# ADC.net
KiCad netlist of a schematic drawn in EasyEDA Pro
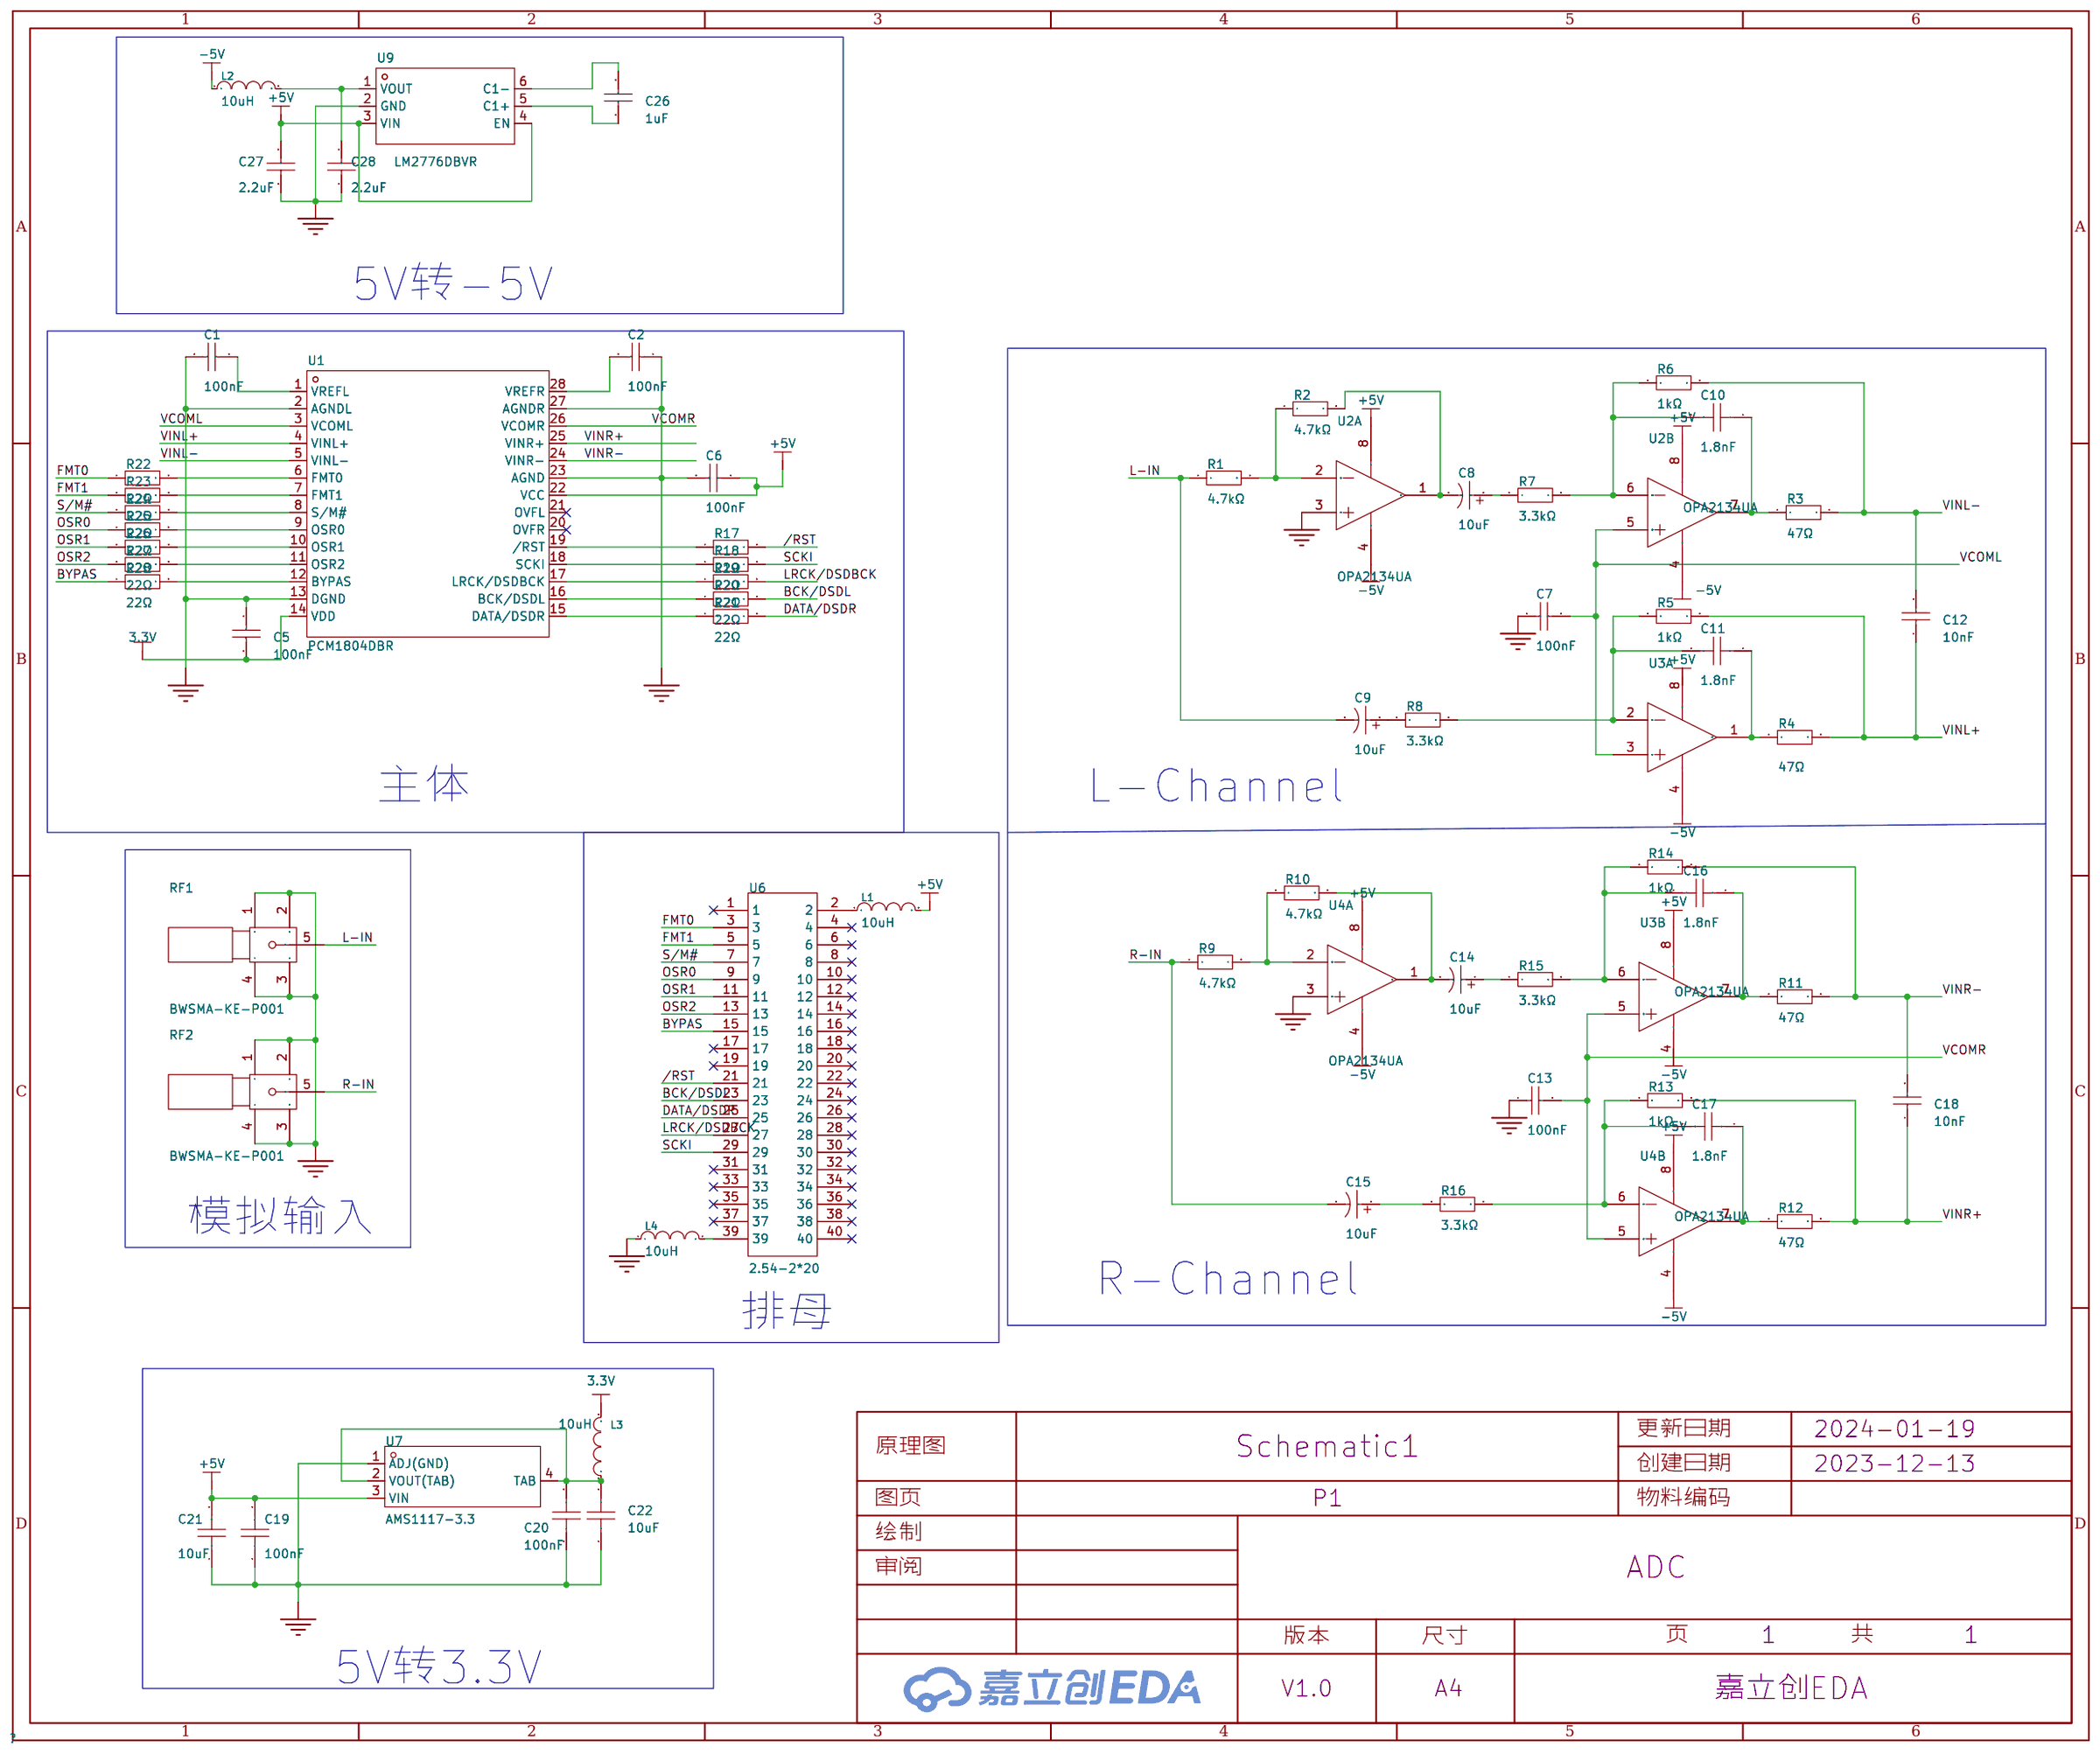
[diagram p0: schematic sheet]

(export (version "E")
  (design (tool "Eeschema 10.0.6"))
  (components
    (comp (ref "C1")
      (value "100nF")
      (footprint "easyedapro:C0805")
      (description "容值:100nF;精度:±10%;额定电压:50V;材质(温度系数):X7R;")
      (fields
        (field (name "Manufacturer Part") "CC0805KRX7R9BB104")
        (field (name "Manufacturer") "YAGEO(国巨)")
      )
      (libsource (lib "easyedapro") (part "CC0805KRX7R9BB104"))
    )
    (comp (ref "C2")
      (value "100nF")
      (footprint "easyedapro:C0805")
      (description "容值:100nF;精度:±10%;额定电压:50V;材质(温度系数):X7R;")
      (fields
        (field (name "Manufacturer Part") "CC0805KRX7R9BB104")
        (field (name "Manufacturer") "YAGEO(国巨)")
      )
      (libsource (lib "easyedapro") (part "CC0805KRX7R9BB104"))
    )
    (comp (ref "C5")
      (value "100nF")
      (footprint "easyedapro:C0805")
      (description "容值:100nF;精度:±10%;额定电压:50V;材质(温度系数):X7R;")
      (fields
        (field (name "Manufacturer Part") "CC0805KRX7R9BB104")
        (field (name "Manufacturer") "YAGEO(国巨)")
      )
      (libsource (lib "easyedapro") (part "CC0805KRX7R9BB104"))
    )
    (comp (ref "C6")
      (value "100nF")
      (footprint "easyedapro:C0805")
      (description "容值:100nF;精度:±10%;额定电压:50V;材质(温度系数):X7R;")
      (fields
        (field (name "Manufacturer Part") "CC0805KRX7R9BB104")
        (field (name "Manufacturer") "YAGEO(国巨)")
      )
      (libsource (lib "easyedapro") (part "CC0805KRX7R9BB104"))
    )
    (comp (ref "C7")
      (value "100nF")
      (footprint "easyedapro:C0805")
      (description "容值:100nF;精度:±10%;额定电压:50V;材质(温度系数):X7R;")
      (fields
        (field (name "Manufacturer Part") "CC0805KRX7R9BB104")
        (field (name "Manufacturer") "YAGEO(国巨)")
      )
      (libsource (lib "easyedapro") (part "CC0805KRX7R9BB104"))
    )
    (comp (ref "C8")
      (value "10uF")
      (footprint "easyedapro:CAP-SMD_BD6.3-L6.6-W6.6-FD")
      (description "容值:10uF;精度:±20%;额定电压:100V;纹波电流:38mA@120Hz;等效串联电阻:-;")
      (fields (field (name "Manufacturer Part") "RVT2A100M0607") (field (name "Manufacturer") "ROQANG(容强)"))
      (libsource (lib "easyedapro") (part "RVT2A100M0607"))
    )
    (comp (ref "C9")
      (value "10uF")
      (footprint "easyedapro:CAP-SMD_BD6.3-L6.6-W6.6-FD")
      (description "容值:10uF;精度:±20%;额定电压:100V;纹波电流:38mA@120Hz;等效串联电阻:-;")
      (fields (field (name "Manufacturer Part") "RVT2A100M0607") (field (name "Manufacturer") "ROQANG(容强)"))
      (libsource (lib "easyedapro") (part "RVT2A100M0607"))
    )
    (comp (ref "C10")
      (value "1.8nF")
      (footprint "easyedapro:C0201")
      (description "容值:1.8nF;精度:±10%;额定电压:25V;材质(温度系数):X7R;")
      (fields
        (field (name "Manufacturer Part") "CC0805JRNPO9BN182")
        (field (name "Manufacturer") "YAGEO(国巨)")
      )
      (libsource (lib "easyedapro") (part "GRM033R71E182KA12D"))
    )
    (comp (ref "C11")
      (value "1.8nF")
      (footprint "easyedapro:C0201")
      (description "容值:1.8nF;精度:±10%;额定电压:25V;材质(温度系数):X7R;")
      (fields
        (field (name "Manufacturer Part") "CC0805JRNPO9BN182")
        (field (name "Manufacturer") "YAGEO(国巨)")
      )
      (libsource (lib "easyedapro") (part "GRM033R71E182KA12D"))
    )
    (comp (ref "C12")
      (value "10nF")
      (footprint "easyedapro:C0402")
      (description "容值:10nF;精度:±10%;额定电压:50V;材质(温度系数):X7R;")
      (fields
        (field (name "Manufacturer Part") "CL21B103KBANNNC")
        (field (name "Manufacturer") "SAMSUNG(三星)")
      )
      (libsource (lib "easyedapro") (part "CC0402KRX7R9BB103"))
    )
    (comp (ref "C13")
      (value "100nF")
      (footprint "easyedapro:C0805")
      (description "容值:100nF;精度:±10%;额定电压:50V;材质(温度系数):X7R;")
      (fields
        (field (name "Manufacturer Part") "CC0805KRX7R9BB104")
        (field (name "Manufacturer") "YAGEO(国巨)")
      )
      (libsource (lib "easyedapro") (part "CC0805KRX7R9BB104"))
    )
    (comp (ref "C14")
      (value "10uF")
      (footprint "easyedapro:CAP-SMD_BD6.3-L6.6-W6.6-FD")
      (description "容值:10uF;精度:±20%;额定电压:100V;纹波电流:38mA@120Hz;等效串联电阻:-;")
      (fields (field (name "Manufacturer Part") "RVT2A100M0607") (field (name "Manufacturer") "ROQANG(容强)"))
      (libsource (lib "easyedapro") (part "RVT2A100M0607"))
    )
    (comp (ref "C15")
      (value "10uF")
      (footprint "easyedapro:CAP-SMD_BD6.3-L6.6-W6.6-FD")
      (description "容值:10uF;精度:±20%;额定电压:100V;纹波电流:38mA@120Hz;等效串联电阻:-;")
      (fields (field (name "Manufacturer Part") "RVT2A100M0607") (field (name "Manufacturer") "ROQANG(容强)"))
      (libsource (lib "easyedapro") (part "RVT2A100M0607"))
    )
    (comp (ref "C16")
      (value "1.8nF")
      (footprint "easyedapro:C0201")
      (description "容值:1.8nF;精度:±10%;额定电压:25V;材质(温度系数):X7R;")
      (fields
        (field (name "Manufacturer Part") "CC0805JRNPO9BN182")
        (field (name "Manufacturer") "YAGEO(国巨)")
      )
      (libsource (lib "easyedapro") (part "GRM033R71E182KA12D"))
    )
    (comp (ref "C17")
      (value "1.8nF")
      (footprint "easyedapro:C0201")
      (description "容值:1.8nF;精度:±10%;额定电压:25V;材质(温度系数):X7R;")
      (fields
        (field (name "Manufacturer Part") "CC0805JRNPO9BN182")
        (field (name "Manufacturer") "YAGEO(国巨)")
      )
      (libsource (lib "easyedapro") (part "GRM033R71E182KA12D"))
    )
    (comp (ref "C18")
      (value "10nF")
      (footprint "easyedapro:C0402")
      (description "容值:10nF;精度:±10%;额定电压:50V;材质(温度系数):X7R;")
      (fields
        (field (name "Manufacturer Part") "CL21B103KBANNNC")
        (field (name "Manufacturer") "SAMSUNG(三星)")
      )
      (libsource (lib "easyedapro") (part "CC0402KRX7R9BB103"))
    )
    (comp (ref "C19")
      (value "100nF")
      (footprint "easyedapro:C0603")
      (description "容值:100nF;精度:±10%;额定电压:50V;材质(温度系数):X7R;")
      (fields
        (field (name "Manufacturer Part") "CC0805KRX7R9BB104")
        (field (name "Manufacturer") "YAGEO(国巨)")
      )
      (libsource (lib "easyedapro") (part "CC0603KRX7R9BB104"))
    )
    (comp (ref "C20")
      (value "100nF")
      (footprint "easyedapro:C0603")
      (description "容值:100nF;精度:±10%;额定电压:50V;材质(温度系数):X7R;")
      (fields
        (field (name "Manufacturer Part") "CC0805KRX7R9BB104")
        (field (name "Manufacturer") "YAGEO(国巨)")
      )
      (libsource (lib "easyedapro") (part "CC0603KRX7R9BB104"))
    )
    (comp (ref "C21")
      (value "10uF")
      (footprint "easyedapro:C0603")
      (description "容值:10uF;精度:±10%;额定电压:10V;材质(温度系数):X5R;")
      (fields
        (field (name "Manufacturer Part") "CL21A106KAYNNNE")
        (field (name "Manufacturer") "SAMSUNG(三星)")
      )
      (libsource (lib "easyedapro") (part "CL10A106KP8NNNC"))
    )
    (comp (ref "C22")
      (value "10uF")
      (footprint "easyedapro:C0603")
      (description "容值:10uF;精度:±10%;额定电压:10V;材质(温度系数):X5R;")
      (fields
        (field (name "Manufacturer Part") "CL21A106KAYNNNE")
        (field (name "Manufacturer") "SAMSUNG(三星)")
      )
      (libsource (lib "easyedapro") (part "CL10A106KP8NNNC"))
    )
    (comp (ref "C26")
      (value "1uF")
      (footprint "easyedapro:C0603")
      (description "容值:1uF;精度:±10%;额定电压:50V;材质(温度系数):X5R;")
      (fields
        (field (name "Manufacturer Part") "CL21B105KBFNNNE")
        (field (name "Manufacturer") "SAMSUNG(三星)")
      )
      (libsource (lib "easyedapro") (part "CL10A105KB8NNNC"))
    )
    (comp (ref "C27")
      (value "2.2uF")
      (footprint "easyedapro:C0603")
      (description "容值:2.2uF;精度:±10%;额定电压:16V;材质(温度系数):X5R;")
      (fields
        (field (name "Manufacturer Part") "CL21A225KBQNNNE")
        (field (name "Manufacturer") "SAMSUNG(三星)")
      )
      (libsource (lib "easyedapro") (part "CL10A225KO8NNNC"))
    )
    (comp (ref "C28")
      (value "2.2uF")
      (footprint "easyedapro:C0603")
      (description "容值:2.2uF;精度:±10%;额定电压:16V;材质(温度系数):X5R;")
      (fields
        (field (name "Manufacturer Part") "CL21A225KBQNNNE")
        (field (name "Manufacturer") "SAMSUNG(三星)")
      )
      (libsource (lib "easyedapro") (part "CL10A225KO8NNNC"))
    )
    (comp (ref "L1")
      (value "10uH")
      (footprint "easyedapro:L0603")
      (description "电感值:10uH;精度:±10%;额定电流:3mA;饱和电流(Isat):-;直流电阻(DCR):1.85Ω;")
      (fields
        (field (name "Manufacturer Part") "SDFL2012S100KTF")
        (field (name "Manufacturer") "Sunlord(顺络)")
      )
      (libsource (lib "easyedapro") (part "SDFL1608S100KTF"))
    )
    (comp (ref "L2")
      (value "10uH")
      (footprint "easyedapro:L0603")
      (description "电感值:10uH;精度:±10%;额定电流:3mA;饱和电流(Isat):-;直流电阻(DCR):1.85Ω;")
      (fields
        (field (name "Manufacturer Part") "SDFL2012S100KTF")
        (field (name "Manufacturer") "Sunlord(顺络)")
      )
      (libsource (lib "easyedapro") (part "SDFL1608S100KTF"))
    )
    (comp (ref "L3")
      (value "10uH")
      (footprint "easyedapro:L0603")
      (description "电感值:10uH;精度:±10%;额定电流:3mA;饱和电流(Isat):-;直流电阻(DCR):1.85Ω;")
      (fields
        (field (name "Manufacturer Part") "SDFL2012S100KTF")
        (field (name "Manufacturer") "Sunlord(顺络)")
      )
      (libsource (lib "easyedapro") (part "SDFL1608S100KTF"))
    )
    (comp (ref "L4")
      (value "10uH")
      (footprint "easyedapro:L0603")
      (description "电感值:10uH;精度:±10%;额定电流:3mA;饱和电流(Isat):-;直流电阻(DCR):1.85Ω;")
      (fields
        (field (name "Manufacturer Part") "SDFL2012S100KTF")
        (field (name "Manufacturer") "Sunlord(顺络)")
      )
      (libsource (lib "easyedapro") (part "SDFL1608S100KTF"))
    )
    (comp (ref "R1")
      (value "4.7kΩ")
      (footprint "easyedapro:R0603")
      (description "阻值:4.7kΩ;精度:±1%;功率:100mW;温度系数:±100ppm/°C;电阻类型:厚膜电阻;")
      (fields
        (field (name "Manufacturer Part") "0805W8F4701T5E")
        (field (name "Manufacturer") "UNI-ROYAL(厚声)")
      )
      (libsource (lib "easyedapro") (part "0603WAF4701T5E"))
    )
    (comp (ref "R2")
      (value "4.7kΩ")
      (footprint "easyedapro:R0603")
      (description "阻值:4.7kΩ;精度:±1%;功率:100mW;温度系数:±100ppm/°C;电阻类型:厚膜电阻;")
      (fields
        (field (name "Manufacturer Part") "0805W8F4701T5E")
        (field (name "Manufacturer") "UNI-ROYAL(厚声)")
      )
      (libsource (lib "easyedapro") (part "0603WAF4701T5E"))
    )
    (comp (ref "R3")
      (value "47Ω")
      (footprint "easyedapro:R0603")
      (description "阻值:47kΩ;精度:±1%;功率:100mW;温度系数:±100ppm/°C;电阻类型:厚膜电阻;")
      (fields
        (field (name "Manufacturer Part") "0805W8F4702T5E")
        (field (name "Manufacturer") "UNI-ROYAL(厚声)")
      )
      (libsource (lib "easyedapro") (part "0603WAF4702T5E"))
    )
    (comp (ref "R4")
      (value "47Ω")
      (footprint "easyedapro:R0603")
      (description "阻值:47kΩ;精度:±1%;功率:100mW;温度系数:±100ppm/°C;电阻类型:厚膜电阻;")
      (fields
        (field (name "Manufacturer Part") "0805W8F4702T5E")
        (field (name "Manufacturer") "UNI-ROYAL(厚声)")
      )
      (libsource (lib "easyedapro") (part "0603WAF4702T5E"))
    )
    (comp (ref "R5")
      (value "1kΩ")
      (footprint "easyedapro:R0805")
      (description "阻值:1kΩ;精度:±1%;功率:125mW;温度系数:±100ppm/°C;电阻类型:厚膜电阻;")
      (fields
        (field (name "Manufacturer Part") "0805W8F1001T5E")
        (field (name "Manufacturer") "UNI-ROYAL(厚声)")
      )
      (libsource (lib "easyedapro") (part "0805W8F1001T5E"))
    )
    (comp (ref "R6")
      (value "1kΩ")
      (footprint "easyedapro:R0805")
      (description "阻值:1kΩ;精度:±1%;功率:125mW;温度系数:±100ppm/°C;电阻类型:厚膜电阻;")
      (fields
        (field (name "Manufacturer Part") "0805W8F1001T5E")
        (field (name "Manufacturer") "UNI-ROYAL(厚声)")
      )
      (libsource (lib "easyedapro") (part "0805W8F1001T5E"))
    )
    (comp (ref "R7")
      (value "3.3kΩ")
      (footprint "easyedapro:R0603")
      (description "阻值:3.3kΩ;精度:±1%;功率:100mW;温度系数:±100ppm/°C;电阻类型:厚膜电阻;")
      (fields
        (field (name "Manufacturer Part") "0805W8F3301T5E")
        (field (name "Manufacturer") "UNI-ROYAL(厚声)")
      )
      (libsource (lib "easyedapro") (part "0603WAF3301T5E"))
    )
    (comp (ref "R8")
      (value "3.3kΩ")
      (footprint "easyedapro:R0603")
      (description "阻值:3.3kΩ;精度:±1%;功率:100mW;温度系数:±100ppm/°C;电阻类型:厚膜电阻;")
      (fields
        (field (name "Manufacturer Part") "0805W8F3301T5E")
        (field (name "Manufacturer") "UNI-ROYAL(厚声)")
      )
      (libsource (lib "easyedapro") (part "0603WAF3301T5E"))
    )
    (comp (ref "R9")
      (value "4.7kΩ")
      (footprint "easyedapro:R0603")
      (description "阻值:4.7kΩ;精度:±1%;功率:100mW;温度系数:±100ppm/°C;电阻类型:厚膜电阻;")
      (fields
        (field (name "Manufacturer Part") "0805W8F4701T5E")
        (field (name "Manufacturer") "UNI-ROYAL(厚声)")
      )
      (libsource (lib "easyedapro") (part "0603WAF4701T5E"))
    )
    (comp (ref "R10")
      (value "4.7kΩ")
      (footprint "easyedapro:R0603")
      (description "阻值:4.7kΩ;精度:±1%;功率:100mW;温度系数:±100ppm/°C;电阻类型:厚膜电阻;")
      (fields
        (field (name "Manufacturer Part") "0805W8F4701T5E")
        (field (name "Manufacturer") "UNI-ROYAL(厚声)")
      )
      (libsource (lib "easyedapro") (part "0603WAF4701T5E"))
    )
    (comp (ref "R11")
      (value "47Ω")
      (footprint "easyedapro:R0603")
      (description "阻值:47kΩ;精度:±1%;功率:100mW;温度系数:±100ppm/°C;电阻类型:厚膜电阻;")
      (fields
        (field (name "Manufacturer Part") "0805W8F4702T5E")
        (field (name "Manufacturer") "UNI-ROYAL(厚声)")
      )
      (libsource (lib "easyedapro") (part "0603WAF4702T5E"))
    )
    (comp (ref "R12")
      (value "47Ω")
      (footprint "easyedapro:R0603")
      (description "阻值:47kΩ;精度:±1%;功率:100mW;温度系数:±100ppm/°C;电阻类型:厚膜电阻;")
      (fields
        (field (name "Manufacturer Part") "0805W8F4702T5E")
        (field (name "Manufacturer") "UNI-ROYAL(厚声)")
      )
      (libsource (lib "easyedapro") (part "0603WAF4702T5E"))
    )
    (comp (ref "R13")
      (value "1kΩ")
      (footprint "easyedapro:R0805")
      (description "阻值:1kΩ;精度:±1%;功率:125mW;温度系数:±100ppm/°C;电阻类型:厚膜电阻;")
      (fields
        (field (name "Manufacturer Part") "0805W8F1001T5E")
        (field (name "Manufacturer") "UNI-ROYAL(厚声)")
      )
      (libsource (lib "easyedapro") (part "0805W8F1001T5E"))
    )
    (comp (ref "R14")
      (value "1kΩ")
      (footprint "easyedapro:R0805")
      (description "阻值:1kΩ;精度:±1%;功率:125mW;温度系数:±100ppm/°C;电阻类型:厚膜电阻;")
      (fields
        (field (name "Manufacturer Part") "0805W8F1001T5E")
        (field (name "Manufacturer") "UNI-ROYAL(厚声)")
      )
      (libsource (lib "easyedapro") (part "0805W8F1001T5E"))
    )
    (comp (ref "R15")
      (value "3.3kΩ")
      (footprint "easyedapro:R0603")
      (description "阻值:3.3kΩ;精度:±1%;功率:100mW;温度系数:±100ppm/°C;电阻类型:厚膜电阻;")
      (fields
        (field (name "Manufacturer Part") "0805W8F3301T5E")
        (field (name "Manufacturer") "UNI-ROYAL(厚声)")
      )
      (libsource (lib "easyedapro") (part "0603WAF3301T5E"))
    )
    (comp (ref "R16")
      (value "3.3kΩ")
      (footprint "easyedapro:R0603")
      (description "阻值:3.3kΩ;精度:±1%;功率:100mW;温度系数:±100ppm/°C;电阻类型:厚膜电阻;")
      (fields
        (field (name "Manufacturer Part") "0805W8F3301T5E")
        (field (name "Manufacturer") "UNI-ROYAL(厚声)")
      )
      (libsource (lib "easyedapro") (part "0603WAF3301T5E"))
    )
    (comp (ref "R17")
      (value "22Ω")
      (footprint "easyedapro:R0805")
      (description "阻值:22Ω;精度:±1%;功率:125mW;温度系数:±100ppm/°C;电阻类型:厚膜电阻;")
      (fields
        (field (name "Manufacturer Part") "0805W8F220JT5E")
        (field (name "Manufacturer") "UNI-ROYAL(厚声)")
      )
      (libsource (lib "easyedapro") (part "0805W8F220JT5E"))
    )
    (comp (ref "R18")
      (value "22Ω")
      (footprint "easyedapro:R0805")
      (description "阻值:22Ω;精度:±1%;功率:125mW;温度系数:±100ppm/°C;电阻类型:厚膜电阻;")
      (fields
        (field (name "Manufacturer Part") "0805W8F220JT5E")
        (field (name "Manufacturer") "UNI-ROYAL(厚声)")
      )
      (libsource (lib "easyedapro") (part "0805W8F220JT5E"))
    )
    (comp (ref "R19")
      (value "22Ω")
      (footprint "easyedapro:R0805")
      (description "阻值:22Ω;精度:±1%;功率:125mW;温度系数:±100ppm/°C;电阻类型:厚膜电阻;")
      (fields
        (field (name "Manufacturer Part") "0805W8F220JT5E")
        (field (name "Manufacturer") "UNI-ROYAL(厚声)")
      )
      (libsource (lib "easyedapro") (part "0805W8F220JT5E"))
    )
    (comp (ref "R20")
      (value "22Ω")
      (footprint "easyedapro:R0805")
      (description "阻值:22Ω;精度:±1%;功率:125mW;温度系数:±100ppm/°C;电阻类型:厚膜电阻;")
      (fields
        (field (name "Manufacturer Part") "0805W8F220JT5E")
        (field (name "Manufacturer") "UNI-ROYAL(厚声)")
      )
      (libsource (lib "easyedapro") (part "0805W8F220JT5E"))
    )
    (comp (ref "R21")
      (value "22Ω")
      (footprint "easyedapro:R0805")
      (description "阻值:22Ω;精度:±1%;功率:125mW;温度系数:±100ppm/°C;电阻类型:厚膜电阻;")
      (fields
        (field (name "Manufacturer Part") "0805W8F220JT5E")
        (field (name "Manufacturer") "UNI-ROYAL(厚声)")
      )
      (libsource (lib "easyedapro") (part "0805W8F220JT5E"))
    )
    (comp (ref "R22")
      (value "22Ω")
      (footprint "easyedapro:R0805")
      (description "阻值:22Ω;精度:±1%;功率:125mW;温度系数:±100ppm/°C;电阻类型:厚膜电阻;")
      (fields
        (field (name "Manufacturer Part") "0805W8F220JT5E")
        (field (name "Manufacturer") "UNI-ROYAL(厚声)")
      )
      (libsource (lib "easyedapro") (part "0805W8F220JT5E"))
    )
    (comp (ref "R23")
      (value "22Ω")
      (footprint "easyedapro:R0805")
      (description "阻值:22Ω;精度:±1%;功率:125mW;温度系数:±100ppm/°C;电阻类型:厚膜电阻;")
      (fields
        (field (name "Manufacturer Part") "0805W8F220JT5E")
        (field (name "Manufacturer") "UNI-ROYAL(厚声)")
      )
      (libsource (lib "easyedapro") (part "0805W8F220JT5E"))
    )
    (comp (ref "R24")
      (value "22Ω")
      (footprint "easyedapro:R0805")
      (description "阻值:22Ω;精度:±1%;功率:125mW;温度系数:±100ppm/°C;电阻类型:厚膜电阻;")
      (fields
        (field (name "Manufacturer Part") "0805W8F220JT5E")
        (field (name "Manufacturer") "UNI-ROYAL(厚声)")
      )
      (libsource (lib "easyedapro") (part "0805W8F220JT5E"))
    )
    (comp (ref "R25")
      (value "22Ω")
      (footprint "easyedapro:R0805")
      (description "阻值:22Ω;精度:±1%;功率:125mW;温度系数:±100ppm/°C;电阻类型:厚膜电阻;")
      (fields
        (field (name "Manufacturer Part") "0805W8F220JT5E")
        (field (name "Manufacturer") "UNI-ROYAL(厚声)")
      )
      (libsource (lib "easyedapro") (part "0805W8F220JT5E"))
    )
    (comp (ref "R26")
      (value "22Ω")
      (footprint "easyedapro:R0805")
      (description "阻值:22Ω;精度:±1%;功率:125mW;温度系数:±100ppm/°C;电阻类型:厚膜电阻;")
      (fields
        (field (name "Manufacturer Part") "0805W8F220JT5E")
        (field (name "Manufacturer") "UNI-ROYAL(厚声)")
      )
      (libsource (lib "easyedapro") (part "0805W8F220JT5E"))
    )
    (comp (ref "R27")
      (value "22Ω")
      (footprint "easyedapro:R0805")
      (description "阻值:22Ω;精度:±1%;功率:125mW;温度系数:±100ppm/°C;电阻类型:厚膜电阻;")
      (fields
        (field (name "Manufacturer Part") "0805W8F220JT5E")
        (field (name "Manufacturer") "UNI-ROYAL(厚声)")
      )
      (libsource (lib "easyedapro") (part "0805W8F220JT5E"))
    )
    (comp (ref "R28")
      (value "22Ω")
      (footprint "easyedapro:R0805")
      (description "阻值:22Ω;精度:±1%;功率:125mW;温度系数:±100ppm/°C;电阻类型:厚膜电阻;")
      (fields
        (field (name "Manufacturer Part") "0805W8F220JT5E")
        (field (name "Manufacturer") "UNI-ROYAL(厚声)")
      )
      (libsource (lib "easyedapro") (part "0805W8F220JT5E"))
    )
    (comp (ref "RF1")
      (value "BWSMA-KE-P001")
      (footprint "easyedapro:SMA-TH_BWSMA-KWE-Z001")
      (fields (field (name "Manufacturer") "BAT WIRELESS(蝙蝠无线)"))
      (libsource (lib "easyedapro") (part "BWSMA-KWE-Z001"))
    )
    (comp (ref "RF2")
      (value "BWSMA-KE-P001")
      (footprint "easyedapro:SMA-TH_BWSMA-KWE-Z001")
      (fields (field (name "Manufacturer") "BAT WIRELESS(蝙蝠无线)"))
      (libsource (lib "easyedapro") (part "BWSMA-KWE-Z001"))
    )
    (comp (ref "U1")
      (value "PCM1804DBR")
      (footprint "easyedapro:SSOP-28_L10.2-W5.3-P0.65-LS7.8-BL")
      (description "供电电压:3V~3.6V；4.75V~5.25V;分辨率(位):24;接口类型:I2S;")
      (fields (field (name "Manufacturer") "TI(德州仪器)"))
      (libsource (lib "easyedapro") (part "PCM1804DBR"))
    )
    (comp (ref "U2")
      (value "OPA2134UA")
      (footprint "easyedapro:DIP-8_L9.6-W6.4-P2.54-LS7.6-BL-1")
      (description "功放类型:-;输出功率:-;")
      (fields (field (name "Manufacturer") "TI(德州仪器)"))
      (libsource (lib "easyedapro") (part "OPA2134PA"))
    )
    (comp (ref "U3")
      (value "OPA2134UA")
      (footprint "easyedapro:DIP-8_L9.6-W6.4-P2.54-LS7.6-BL-1")
      (description "功放类型:-;输出功率:-;")
      (fields (field (name "Manufacturer") "TI(德州仪器)"))
      (libsource (lib "easyedapro") (part "OPA2134PA"))
    )
    (comp (ref "U4")
      (value "OPA2134UA")
      (footprint "easyedapro:DIP-8_L9.6-W6.4-P2.54-LS7.6-BL-1")
      (description "功放类型:-;输出功率:-;")
      (fields (field (name "Manufacturer") "TI(德州仪器)"))
      (libsource (lib "easyedapro") (part "OPA2134PA"))
    )
    (comp (ref "U6")
      (value "2.54-2*20")
      (footprint "easyedapro:HDR-TH_40P-P2.54-V-F-R2-C20-S2.54")
      (fields (field (name "Manufacturer") "ZHOURI(洲日)"))
      (libsource (lib "easyedapro") (part "2.54-2*20"))
    )
    (comp (ref "U7")
      (value "AMS1117-3.3")
      (footprint "easyedapro:SOT-223-4_L6.5-W3.5-P2.30-LS7.0-BR")
      (description "输出类型:固定;最大输入电压:18V;输出电压:3.3V;输出电流:1A;电源纹波抑制比(PSRR):60dB@(120Hz);输出极性:正;")
      (fields (field (name "Manufacturer") "UMW(友台半导体)"))
      (libsource (lib "easyedapro") (part "AMS1117-3.3_C347222"))
    )
    (comp (ref "U9")
      (value "LM2776DBVR")
      (footprint "easyedapro:SOT-23-6_L2.9-W1.6-P0.95-LS2.8-BR")
      (description "功能类型:电荷泵;输出类型:固定;输入电压:2.7V~5.5V;输出电压:-5.5V~-2.7V;输出电流(最大值):200mA;")
      (fields (field (name "Manufacturer") "TI(德州仪器)"))
      (libsource (lib "easyedapro") (part "LM2776DBVR"))
    )
  )
  (nets
    (net (code "1") (name "+5V") (class "Default")
      (node (ref "C19") (pin "2") (pinfunction "2_2") (pintype "unspecified"))
      (node (ref "C21") (pin "2") (pinfunction "2_2") (pintype "unspecified"))
      (node (ref "C27") (pin "2") (pinfunction "2_2") (pintype "input"))
      (node (ref "C6") (pin "1") (pinfunction "1_1") (pintype "input"))
      (node (ref "L1") (pin "2") (pinfunction "2_2") (pintype "input"))
      (node (ref "U1") (pin "22") (pinfunction "VCC_22") (pintype "unspecified"))
      (node (ref "U2") (pin "8") (pinfunction "V+_8") (pintype "input"))
      (node (ref "U3") (pin "8") (pinfunction "V+_8") (pintype "input"))
      (node (ref "U4") (pin "8") (pinfunction "V+_8") (pintype "input"))
      (node (ref "U7") (pin "3") (pinfunction "VIN_3") (pintype "unspecified"))
      (node (ref "U9") (pin "3") (pinfunction "VIN_3") (pintype "unspecified"))
      (node (ref "U9") (pin "4") (pinfunction "EN_4") (pintype "unspecified"))
    )
    (net (code "2") (name "-5V") (class "Default")
      (node (ref "L2") (pin "1") (pinfunction "1_1") (pintype "input"))
      (node (ref "U2") (pin "4") (pinfunction "V-_4") (pintype "input"))
      (node (ref "U3") (pin "4") (pinfunction "V-_4") (pintype "input"))
      (node (ref "U4") (pin "4") (pinfunction "V-_4") (pintype "input"))
    )
    (net (code "3") (name "/BCK{slash}DSDL") (class "Default")
      (node (ref "R20") (pin "2") (pinfunction "2_2") (pintype "input"))
      (node (ref "U6") (pin "23") (pinfunction "23_23") (pintype "unspecified"))
    )
    (net (code "4") (name "/BYPAS") (class "Default")
      (node (ref "R28") (pin "1") (pinfunction "1_1") (pintype "input"))
      (node (ref "U6") (pin "15") (pinfunction "15_15") (pintype "unspecified"))
    )
    (net (code "5") (name "/DATA{slash}DSDR") (class "Default")
      (node (ref "R21") (pin "2") (pinfunction "2_2") (pintype "input"))
      (node (ref "U6") (pin "25") (pinfunction "25_25") (pintype "unspecified"))
    )
    (net (code "6") (name "/FMT0") (class "Default")
      (node (ref "R22") (pin "1") (pinfunction "1_1") (pintype "input"))
      (node (ref "U6") (pin "3") (pinfunction "3_3") (pintype "unspecified"))
    )
    (net (code "7") (name "/FMT1") (class "Default")
      (node (ref "R23") (pin "1") (pinfunction "1_1") (pintype "input"))
      (node (ref "U6") (pin "5") (pinfunction "5_5") (pintype "unspecified"))
    )
    (net (code "8") (name "/L-IN") (class "Default")
      (node (ref "C9") (pin "2") (pinfunction "2_2") (pintype "input"))
      (node (ref "R1") (pin "1") (pinfunction "1_1") (pintype "input"))
      (node (ref "RF1") (pin "5") (pinfunction "5_5") (pintype "unspecified"))
    )
    (net (code "9") (name "/LRCK{slash}DSDBCK") (class "Default")
      (node (ref "R19") (pin "2") (pinfunction "2_2") (pintype "input"))
      (node (ref "U6") (pin "27") (pinfunction "27_27") (pintype "unspecified"))
    )
    (net (code "10") (name "/OSR0") (class "Default")
      (node (ref "R25") (pin "1") (pinfunction "1_1") (pintype "input"))
      (node (ref "U6") (pin "9") (pinfunction "9_9") (pintype "unspecified"))
    )
    (net (code "11") (name "/OSR1") (class "Default")
      (node (ref "R26") (pin "1") (pinfunction "1_1") (pintype "input"))
      (node (ref "U6") (pin "11") (pinfunction "11_11") (pintype "unspecified"))
    )
    (net (code "12") (name "/OSR2") (class "Default")
      (node (ref "R27") (pin "1") (pinfunction "1_1") (pintype "input"))
      (node (ref "U6") (pin "13") (pinfunction "13_13") (pintype "unspecified"))
    )
    (net (code "13") (name "/R-IN") (class "Default")
      (node (ref "C15") (pin "2") (pinfunction "2_2") (pintype "input"))
      (node (ref "R9") (pin "1") (pinfunction "1_1") (pintype "input"))
      (node (ref "RF2") (pin "5") (pinfunction "5_5") (pintype "unspecified"))
    )
    (net (code "14") (name "/SCKI") (class "Default")
      (node (ref "R18") (pin "2") (pinfunction "2_2") (pintype "input"))
      (node (ref "U6") (pin "29") (pinfunction "29_29") (pintype "unspecified"))
    )
    (net (code "15") (name "/S{slash}M#") (class "Default")
      (node (ref "R24") (pin "1") (pinfunction "1_1") (pintype "input"))
      (node (ref "U6") (pin "7") (pinfunction "7_7") (pintype "unspecified"))
    )
    (net (code "16") (name "/VCOML") (class "Default")
      (node (ref "C7") (pin "2") (pinfunction "2_2") (pintype "input"))
      (node (ref "U1") (pin "3") (pinfunction "VCOML_3") (pintype "unspecified"))
      (node (ref "U2") (pin "5") (pinfunction "+IN_B_5") (pintype "input"))
      (node (ref "U3") (pin "3") (pinfunction "+IN_A_3") (pintype "input"))
    )
    (net (code "17") (name "/VCOMR") (class "Default")
      (node (ref "C13") (pin "2") (pinfunction "2_2") (pintype "input"))
      (node (ref "U1") (pin "26") (pinfunction "VCOMR_26") (pintype "unspecified"))
      (node (ref "U3") (pin "5") (pinfunction "+IN_B_5") (pintype "input"))
      (node (ref "U4") (pin "5") (pinfunction "+IN_B_5") (pintype "input"))
    )
    (net (code "18") (name "/VINL+") (class "Default")
      (node (ref "C12") (pin "1") (pinfunction "1_1") (pintype "input"))
      (node (ref "R4") (pin "2") (pinfunction "2_2") (pintype "input"))
      (node (ref "R5") (pin "2") (pinfunction "2_2") (pintype "input"))
      (node (ref "U1") (pin "4") (pinfunction "VINL+_4") (pintype "unspecified"))
    )
    (net (code "19") (name "/VINL-") (class "Default")
      (node (ref "C12") (pin "2") (pinfunction "2_2") (pintype "input"))
      (node (ref "R3") (pin "2") (pinfunction "2_2") (pintype "input"))
      (node (ref "R6") (pin "2") (pinfunction "2_2") (pintype "input"))
      (node (ref "U1") (pin "5") (pinfunction "VINL-_5") (pintype "unspecified"))
    )
    (net (code "20") (name "/VINR+") (class "Default")
      (node (ref "C18") (pin "1") (pinfunction "1_1") (pintype "input"))
      (node (ref "R12") (pin "2") (pinfunction "2_2") (pintype "input"))
      (node (ref "R13") (pin "2") (pinfunction "2_2") (pintype "input"))
      (node (ref "U1") (pin "25") (pinfunction "VINR+_25") (pintype "unspecified"))
    )
    (net (code "21") (name "/VINR-") (class "Default")
      (node (ref "C18") (pin "2") (pinfunction "2_2") (pintype "input"))
      (node (ref "R11") (pin "2") (pinfunction "2_2") (pintype "input"))
      (node (ref "R14") (pin "2") (pinfunction "2_2") (pintype "input"))
      (node (ref "U1") (pin "24") (pinfunction "VINR-_24") (pintype "unspecified"))
    )
    (net (code "22") (name "/{slash}RST") (class "Default")
      (node (ref "R17") (pin "2") (pinfunction "2_2") (pintype "input"))
      (node (ref "U6") (pin "21") (pinfunction "21_21") (pintype "unspecified"))
    )
    (net (code "23") (name "3.3V") (class "Default")
      (node (ref "C5") (pin "2") (pinfunction "2_2") (pintype "input"))
      (node (ref "L3") (pin "2") (pinfunction "2_2") (pintype "input"))
      (node (ref "U1") (pin "14") (pinfunction "VDD_14") (pintype "unspecified"))
    )
    (net (code "24") (name "GND") (class "Default")
      (node (ref "C1") (pin "2") (pinfunction "2_2") (pintype "input"))
      (node (ref "C13") (pin "1") (pinfunction "1_1") (pintype "input"))
      (node (ref "C19") (pin "1") (pinfunction "1_1") (pintype "unspecified"))
      (node (ref "C2") (pin "1") (pinfunction "1_1") (pintype "input"))
      (node (ref "C20") (pin "1") (pinfunction "1_1") (pintype "unspecified"))
      (node (ref "C21") (pin "1") (pinfunction "1_1") (pintype "unspecified"))
      (node (ref "C22") (pin "1") (pinfunction "1_1") (pintype "unspecified"))
      (node (ref "C27") (pin "1") (pinfunction "1_1") (pintype "input"))
      (node (ref "C28") (pin "1") (pinfunction "1_1") (pintype "input"))
      (node (ref "C5") (pin "1") (pinfunction "1_1") (pintype "input"))
      (node (ref "C6") (pin "2") (pinfunction "2_2") (pintype "input"))
      (node (ref "C7") (pin "1") (pinfunction "1_1") (pintype "input"))
      (node (ref "L4") (pin "1") (pinfunction "1_1") (pintype "input"))
      (node (ref "RF1") (pin "1") (pinfunction "1_1") (pintype "unspecified"))
      (node (ref "RF1") (pin "2") (pinfunction "2_2") (pintype "unspecified"))
      (node (ref "RF1") (pin "3") (pinfunction "3_3") (pintype "unspecified"))
      (node (ref "RF1") (pin "4") (pinfunction "4_4") (pintype "unspecified"))
      (node (ref "RF2") (pin "1") (pinfunction "1_1") (pintype "unspecified"))
      (node (ref "RF2") (pin "2") (pinfunction "2_2") (pintype "unspecified"))
      (node (ref "RF2") (pin "3") (pinfunction "3_3") (pintype "unspecified"))
      (node (ref "RF2") (pin "4") (pinfunction "4_4") (pintype "unspecified"))
      (node (ref "U1") (pin "13") (pinfunction "DGND_13") (pintype "unspecified"))
      (node (ref "U1") (pin "2") (pinfunction "AGNDL_2") (pintype "unspecified"))
      (node (ref "U1") (pin "23") (pinfunction "AGND_23") (pintype "unspecified"))
      (node (ref "U1") (pin "27") (pinfunction "AGNDR_27") (pintype "unspecified"))
      (node (ref "U2") (pin "3") (pinfunction "+IN_A_3") (pintype "input"))
      (node (ref "U4") (pin "3") (pinfunction "+IN_A_3") (pintype "input"))
      (node (ref "U7") (pin "1") (pinfunction "ADJ(GND)_1") (pintype "unspecified"))
      (node (ref "U9") (pin "2") (pinfunction "GND_2") (pintype "unspecified"))
    )
    (net (code "25") (name "Net-(C8-Pad1)") (class "Default")
      (node (ref "C8") (pin "1") (pinfunction "1_1") (pintype "input"))
      (node (ref "R7") (pin "1") (pinfunction "1_1") (pintype "input"))
    )
    (net (code "26") (name "Net-(C9-Pad1)") (class "Default")
      (node (ref "C9") (pin "1") (pinfunction "1_1") (pintype "input"))
      (node (ref "R8") (pin "1") (pinfunction "1_1") (pintype "input"))
    )
    (net (code "27") (name "Net-(C14-Pad1)") (class "Default")
      (node (ref "C14") (pin "1") (pinfunction "1_1") (pintype "input"))
      (node (ref "R15") (pin "1") (pinfunction "1_1") (pintype "input"))
    )
    (net (code "28") (name "Net-(C15-Pad1)") (class "Default")
      (node (ref "C15") (pin "1") (pinfunction "1_1") (pintype "input"))
      (node (ref "R16") (pin "1") (pinfunction "1_1") (pintype "input"))
    )
    (net (code "29") (name "Net-(L1-Pad1)") (class "Default")
      (node (ref "L1") (pin "1") (pinfunction "1_1") (pintype "input"))
      (node (ref "U6") (pin "2") (pinfunction "2_2") (pintype "unspecified"))
    )
    (net (code "30") (name "Net-(L4-Pad2)") (class "Default")
      (node (ref "L4") (pin "2") (pinfunction "2_2") (pintype "input"))
      (node (ref "U6") (pin "39") (pinfunction "39_39") (pintype "unspecified"))
    )
    (net (code "31") (name "Net-(U1-BCK{slash}DSDL)") (class "Default")
      (node (ref "R20") (pin "1") (pinfunction "1_1") (pintype "input"))
      (node (ref "U1") (pin "16") (pinfunction "BCK/DSDL_16") (pintype "unspecified"))
    )
    (net (code "32") (name "Net-(U1-BYPAS)") (class "Default")
      (node (ref "R28") (pin "2") (pinfunction "2_2") (pintype "input"))
      (node (ref "U1") (pin "12") (pinfunction "BYPAS_12") (pintype "unspecified"))
    )
    (net (code "33") (name "Net-(U1-DATA{slash}DSDR)") (class "Default")
      (node (ref "R21") (pin "1") (pinfunction "1_1") (pintype "input"))
      (node (ref "U1") (pin "15") (pinfunction "DATA/DSDR_15") (pintype "unspecified"))
    )
    (net (code "34") (name "Net-(U1-FMT0)") (class "Default")
      (node (ref "R22") (pin "2") (pinfunction "2_2") (pintype "input"))
      (node (ref "U1") (pin "6") (pinfunction "FMT0_6") (pintype "unspecified"))
    )
    (net (code "35") (name "Net-(U1-FMT1)") (class "Default")
      (node (ref "R23") (pin "2") (pinfunction "2_2") (pintype "input"))
      (node (ref "U1") (pin "7") (pinfunction "FMT1_7") (pintype "unspecified"))
    )
    (net (code "36") (name "Net-(U1-LRCK{slash}DSDBCK)") (class "Default")
      (node (ref "R19") (pin "1") (pinfunction "1_1") (pintype "input"))
      (node (ref "U1") (pin "17") (pinfunction "LRCK/DSDBCK_17") (pintype "unspecified"))
    )
    (net (code "37") (name "Net-(U1-OSR0)") (class "Default")
      (node (ref "R25") (pin "2") (pinfunction "2_2") (pintype "input"))
      (node (ref "U1") (pin "9") (pinfunction "OSR0_9") (pintype "unspecified"))
    )
    (net (code "38") (name "Net-(U1-OSR1)") (class "Default")
      (node (ref "R26") (pin "2") (pinfunction "2_2") (pintype "input"))
      (node (ref "U1") (pin "10") (pinfunction "OSR1_10") (pintype "unspecified"))
    )
    (net (code "39") (name "Net-(U1-OSR2)") (class "Default")
      (node (ref "R27") (pin "2") (pinfunction "2_2") (pintype "input"))
      (node (ref "U1") (pin "11") (pinfunction "OSR2_11") (pintype "unspecified"))
    )
    (net (code "40") (name "Net-(U1-SCKI)") (class "Default")
      (node (ref "R18") (pin "1") (pinfunction "1_1") (pintype "input"))
      (node (ref "U1") (pin "18") (pinfunction "SCKI_18") (pintype "unspecified"))
    )
    (net (code "41") (name "Net-(U1-S{slash}M#)") (class "Default")
      (node (ref "R24") (pin "2") (pinfunction "2_2") (pintype "input"))
      (node (ref "U1") (pin "8") (pinfunction "S/M#_8") (pintype "unspecified"))
    )
    (net (code "42") (name "Net-(U1-VREFL)") (class "Default")
      (node (ref "C1") (pin "1") (pinfunction "1_1") (pintype "input"))
      (node (ref "U1") (pin "1") (pinfunction "VREFL_1") (pintype "unspecified"))
    )
    (net (code "43") (name "Net-(U1-VREFR)") (class "Default")
      (node (ref "C2") (pin "2") (pinfunction "2_2") (pintype "input"))
      (node (ref "U1") (pin "28") (pinfunction "VREFR_28") (pintype "unspecified"))
    )
    (net (code "44") (name "Net-(U1-{slash}RST)") (class "Default")
      (node (ref "R17") (pin "1") (pinfunction "1_1") (pintype "input"))
      (node (ref "U1") (pin "19") (pinfunction "/RST_19") (pintype "unspecified"))
    )
    (net (code "45") (name "Net-(U2A--IN_A)") (class "Default")
      (node (ref "R1") (pin "2") (pinfunction "2_2") (pintype "input"))
      (node (ref "R2") (pin "1") (pinfunction "1_1") (pintype "input"))
      (node (ref "U2") (pin "2") (pinfunction "-IN_A_2") (pintype "input"))
    )
    (net (code "46") (name "Net-(U2A-OUT_A)") (class "Default")
      (node (ref "C8") (pin "2") (pinfunction "2_2") (pintype "input"))
      (node (ref "R2") (pin "2") (pinfunction "2_2") (pintype "input"))
      (node (ref "U2") (pin "1") (pinfunction "OUT_A_1") (pintype "output"))
    )
    (net (code "47") (name "Net-(U2B--IN_B)") (class "Default")
      (node (ref "C10") (pin "2") (pinfunction "2_2") (pintype "unspecified"))
      (node (ref "R6") (pin "1") (pinfunction "1_1") (pintype "input"))
      (node (ref "R7") (pin "2") (pinfunction "2_2") (pintype "input"))
      (node (ref "U2") (pin "6") (pinfunction "-IN_B_6") (pintype "input"))
    )
    (net (code "48") (name "Net-(U2B-OUT_B)") (class "Default")
      (node (ref "C10") (pin "1") (pinfunction "1_1") (pintype "unspecified"))
      (node (ref "R3") (pin "1") (pinfunction "1_1") (pintype "input"))
      (node (ref "U2") (pin "7") (pinfunction "OUT_B_7") (pintype "output"))
    )
    (net (code "49") (name "Net-(U3A--IN_A)") (class "Default")
      (node (ref "C11") (pin "2") (pinfunction "2_2") (pintype "unspecified"))
      (node (ref "R5") (pin "1") (pinfunction "1_1") (pintype "input"))
      (node (ref "R8") (pin "2") (pinfunction "2_2") (pintype "input"))
      (node (ref "U3") (pin "2") (pinfunction "-IN_A_2") (pintype "input"))
    )
    (net (code "50") (name "Net-(U3A-OUT_A)") (class "Default")
      (node (ref "C11") (pin "1") (pinfunction "1_1") (pintype "unspecified"))
      (node (ref "R4") (pin "1") (pinfunction "1_1") (pintype "input"))
      (node (ref "U3") (pin "1") (pinfunction "OUT_A_1") (pintype "output"))
    )
    (net (code "51") (name "Net-(U3B--IN_B)") (class "Default")
      (node (ref "C16") (pin "2") (pinfunction "2_2") (pintype "unspecified"))
      (node (ref "R14") (pin "1") (pinfunction "1_1") (pintype "input"))
      (node (ref "R15") (pin "2") (pinfunction "2_2") (pintype "input"))
      (node (ref "U3") (pin "6") (pinfunction "-IN_B_6") (pintype "input"))
    )
    (net (code "52") (name "Net-(U3B-OUT_B)") (class "Default")
      (node (ref "C16") (pin "1") (pinfunction "1_1") (pintype "unspecified"))
      (node (ref "R11") (pin "1") (pinfunction "1_1") (pintype "input"))
      (node (ref "U3") (pin "7") (pinfunction "OUT_B_7") (pintype "output"))
    )
    (net (code "53") (name "Net-(U4A--IN_A)") (class "Default")
      (node (ref "R10") (pin "1") (pinfunction "1_1") (pintype "input"))
      (node (ref "R9") (pin "2") (pinfunction "2_2") (pintype "input"))
      (node (ref "U4") (pin "2") (pinfunction "-IN_A_2") (pintype "input"))
    )
    (net (code "54") (name "Net-(U4A-OUT_A)") (class "Default")
      (node (ref "C14") (pin "2") (pinfunction "2_2") (pintype "input"))
      (node (ref "R10") (pin "2") (pinfunction "2_2") (pintype "input"))
      (node (ref "U4") (pin "1") (pinfunction "OUT_A_1") (pintype "output"))
    )
    (net (code "55") (name "Net-(U4B--IN_B)") (class "Default")
      (node (ref "C17") (pin "2") (pinfunction "2_2") (pintype "unspecified"))
      (node (ref "R13") (pin "1") (pinfunction "1_1") (pintype "input"))
      (node (ref "R16") (pin "2") (pinfunction "2_2") (pintype "input"))
      (node (ref "U4") (pin "6") (pinfunction "-IN_B_6") (pintype "input"))
    )
    (net (code "56") (name "Net-(U4B-OUT_B)") (class "Default")
      (node (ref "C17") (pin "1") (pinfunction "1_1") (pintype "unspecified"))
      (node (ref "R12") (pin "1") (pinfunction "1_1") (pintype "input"))
      (node (ref "U4") (pin "7") (pinfunction "OUT_B_7") (pintype "output"))
    )
    (net (code "57") (name "Net-(U7-TAB)") (class "Default")
      (node (ref "C20") (pin "2") (pinfunction "2_2") (pintype "unspecified"))
      (node (ref "C22") (pin "2") (pinfunction "2_2") (pintype "unspecified"))
      (node (ref "L3") (pin "1") (pinfunction "1_1") (pintype "input"))
      (node (ref "U7") (pin "2") (pinfunction "VOUT(TAB)_2") (pintype "unspecified"))
      (node (ref "U7") (pin "4") (pinfunction "TAB_4") (pintype "unspecified"))
    )
    (net (code "58") (name "Net-(U9-C1+)") (class "Default")
      (node (ref "C26") (pin "1") (pinfunction "1_1") (pintype "input"))
      (node (ref "U9") (pin "5") (pinfunction "C1+_5") (pintype "unspecified"))
    )
    (net (code "59") (name "Net-(U9-C1-)") (class "Default")
      (node (ref "C26") (pin "2") (pinfunction "2_2") (pintype "input"))
      (node (ref "U9") (pin "6") (pinfunction "C1-_6") (pintype "unspecified"))
    )
    (net (code "60") (name "Net-(U9-VOUT)") (class "Default")
      (node (ref "C28") (pin "2") (pinfunction "2_2") (pintype "input"))
      (node (ref "L2") (pin "2") (pinfunction "2_2") (pintype "input"))
      (node (ref "U9") (pin "1") (pinfunction "VOUT_1") (pintype "unspecified"))
    )
    (net (code "61") (name "unconnected-(U1-OVFL-Pad21)") (class "Default")
      (node (ref "U1") (pin "21") (pinfunction "OVFL_21") (pintype "unspecified+no_connect"))
    )
    (net (code "62") (name "unconnected-(U1-OVFR-Pad20)") (class "Default")
      (node (ref "U1") (pin "20") (pinfunction "OVFR_20") (pintype "unspecified+no_connect"))
    )
    (net (code "63") (name "unconnected-(U6-Pad1)") (class "Default")
      (node (ref "U6") (pin "1") (pinfunction "1_1") (pintype "unspecified+no_connect"))
    )
    (net (code "64") (name "unconnected-(U6-Pad4)") (class "Default")
      (node (ref "U6") (pin "4") (pinfunction "4_4") (pintype "unspecified+no_connect"))
    )
    (net (code "65") (name "unconnected-(U6-Pad6)") (class "Default")
      (node (ref "U6") (pin "6") (pinfunction "6_6") (pintype "unspecified+no_connect"))
    )
    (net (code "66") (name "unconnected-(U6-Pad8)") (class "Default")
      (node (ref "U6") (pin "8") (pinfunction "8_8") (pintype "unspecified+no_connect"))
    )
    (net (code "67") (name "unconnected-(U6-Pad10)") (class "Default")
      (node (ref "U6") (pin "10") (pinfunction "10_10") (pintype "unspecified+no_connect"))
    )
    (net (code "68") (name "unconnected-(U6-Pad12)") (class "Default")
      (node (ref "U6") (pin "12") (pinfunction "12_12") (pintype "unspecified+no_connect"))
    )
    (net (code "69") (name "unconnected-(U6-Pad14)") (class "Default")
      (node (ref "U6") (pin "14") (pinfunction "14_14") (pintype "unspecified+no_connect"))
    )
    (net (code "70") (name "unconnected-(U6-Pad16)") (class "Default")
      (node (ref "U6") (pin "16") (pinfunction "16_16") (pintype "unspecified+no_connect"))
    )
    (net (code "71") (name "unconnected-(U6-Pad17)") (class "Default")
      (node (ref "U6") (pin "17") (pinfunction "17_17") (pintype "unspecified+no_connect"))
    )
    (net (code "72") (name "unconnected-(U6-Pad18)") (class "Default")
      (node (ref "U6") (pin "18") (pinfunction "18_18") (pintype "unspecified+no_connect"))
    )
    (net (code "73") (name "unconnected-(U6-Pad19)") (class "Default")
      (node (ref "U6") (pin "19") (pinfunction "19_19") (pintype "unspecified+no_connect"))
    )
    (net (code "74") (name "unconnected-(U6-Pad20)") (class "Default")
      (node (ref "U6") (pin "20") (pinfunction "20_20") (pintype "unspecified+no_connect"))
    )
    (net (code "75") (name "unconnected-(U6-Pad22)") (class "Default")
      (node (ref "U6") (pin "22") (pinfunction "22_22") (pintype "unspecified+no_connect"))
    )
    (net (code "76") (name "unconnected-(U6-Pad24)") (class "Default")
      (node (ref "U6") (pin "24") (pinfunction "24_24") (pintype "unspecified+no_connect"))
    )
    (net (code "77") (name "unconnected-(U6-Pad26)") (class "Default")
      (node (ref "U6") (pin "26") (pinfunction "26_26") (pintype "unspecified+no_connect"))
    )
    (net (code "78") (name "unconnected-(U6-Pad28)") (class "Default")
      (node (ref "U6") (pin "28") (pinfunction "28_28") (pintype "unspecified+no_connect"))
    )
    (net (code "79") (name "unconnected-(U6-Pad30)") (class "Default")
      (node (ref "U6") (pin "30") (pinfunction "30_30") (pintype "unspecified+no_connect"))
    )
    (net (code "80") (name "unconnected-(U6-Pad31)") (class "Default")
      (node (ref "U6") (pin "31") (pinfunction "31_31") (pintype "unspecified+no_connect"))
    )
    (net (code "81") (name "unconnected-(U6-Pad32)") (class "Default")
      (node (ref "U6") (pin "32") (pinfunction "32_32") (pintype "unspecified+no_connect"))
    )
    (net (code "82") (name "unconnected-(U6-Pad33)") (class "Default")
      (node (ref "U6") (pin "33") (pinfunction "33_33") (pintype "unspecified+no_connect"))
    )
    (net (code "83") (name "unconnected-(U6-Pad34)") (class "Default")
      (node (ref "U6") (pin "34") (pinfunction "34_34") (pintype "unspecified+no_connect"))
    )
    (net (code "84") (name "unconnected-(U6-Pad35)") (class "Default")
      (node (ref "U6") (pin "35") (pinfunction "35_35") (pintype "unspecified+no_connect"))
    )
    (net (code "85") (name "unconnected-(U6-Pad36)") (class "Default")
      (node (ref "U6") (pin "36") (pinfunction "36_36") (pintype "unspecified+no_connect"))
    )
    (net (code "86") (name "unconnected-(U6-Pad37)") (class "Default")
      (node (ref "U6") (pin "37") (pinfunction "37_37") (pintype "unspecified+no_connect"))
    )
    (net (code "87") (name "unconnected-(U6-Pad38)") (class "Default")
      (node (ref "U6") (pin "38") (pinfunction "38_38") (pintype "unspecified+no_connect"))
    )
    (net (code "88") (name "unconnected-(U6-Pad40)") (class "Default")
      (node (ref "U6") (pin "40") (pinfunction "40_40") (pintype "unspecified+no_connect"))
    )
  )
)
